# Mainboard.net
KiCad netlist of a schematic drawn in EAGLE
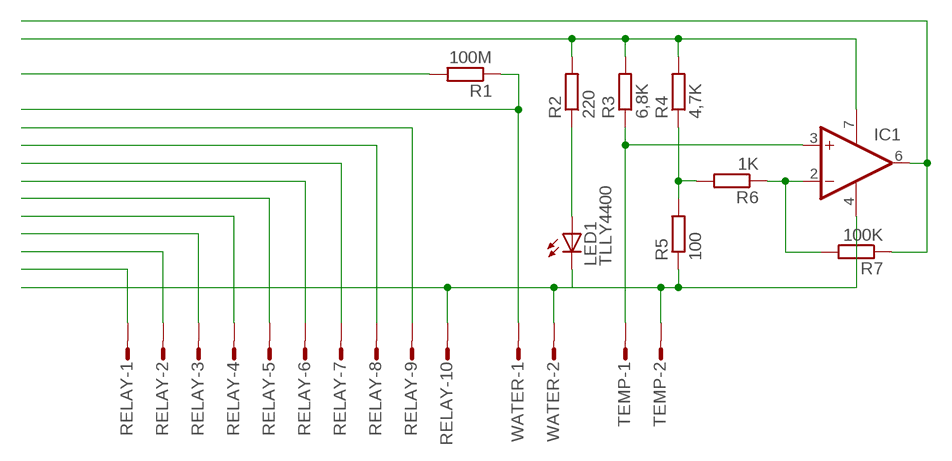
[diagram p0: schematic, sheet 1]

(export (version "E")
  (design (tool "Eeschema 10.0.6"))
  (components
    (comp (ref "IC1")
      (value "1AMP_P7+4N")
      (footprint "eagle-import:DIL08")
      (libsource (lib "eagle-import") (part "1AMP_P7+4N"))
    )
    (comp (ref "LED1")
      (value "TLLY4400")
      (footprint "eagle-import:LED3MM")
      (fields (field (name "MF") "VISHAY SEMICONDUCTOR"))
      (libsource (lib "eagle-import") (part "TLLY4400"))
    )
    (comp (ref "R1")
      (value "100M")
      (footprint "eagle-import:VMTA55")
      (libsource (lib "eagle-import") (part "R-EU_VMTA55"))
    )
    (comp (ref "R2")
      (value "220")
      (footprint "eagle-import:VMTA55")
      (libsource (lib "eagle-import") (part "R-EU_VMTA55"))
    )
    (comp (ref "R3")
      (value "6,8K")
      (footprint "eagle-import:VMTA55")
      (libsource (lib "eagle-import") (part "R-EU_VMTA55"))
    )
    (comp (ref "R4")
      (value "4,7K")
      (footprint "eagle-import:VMTA55")
      (libsource (lib "eagle-import") (part "R-EU_VMTA55"))
    )
    (comp (ref "R5")
      (value "100")
      (footprint "eagle-import:VMTA55")
      (libsource (lib "eagle-import") (part "R-EU_VMTA55"))
    )
    (comp (ref "R6")
      (value "1K")
      (footprint "eagle-import:VMTA55")
      (libsource (lib "eagle-import") (part "R-EU_VMTA55"))
    )
    (comp (ref "R7")
      (value "100K")
      (footprint "eagle-import:VMTA55")
      (libsource (lib "eagle-import") (part "R-EU_VMTA55"))
    )
    (comp (ref "RELAY")
      (value "L10P")
      (footprint "eagle-import:L10P")
      (libsource (lib "eagle-import") (part "L10P"))
    )
    (comp (ref "TEMP")
      (value "L02P")
      (footprint "eagle-import:L02P")
      (libsource (lib "eagle-import") (part "L02P"))
    )
    (comp (ref "WATER")
      (value "L02P")
      (footprint "eagle-import:L02P")
      (libsource (lib "eagle-import") (part "L02P"))
    )
  )
  (nets
    (net (code "1") (name "Net-(IC1-+IN)") (class "Default")
      (node (ref "IC1") (pin "3") (pinfunction "+IN_3") (pintype "input"))
      (node (ref "R3") (pin "1") (pinfunction "1_1") (pintype "passive"))
      (node (ref "TEMP") (pin "1") (pinfunction "S_1") (pintype "passive"))
    )
    (net (code "2") (name "Net-(IC1--IN)") (class "Default")
      (node (ref "IC1") (pin "2") (pinfunction "-IN_2") (pintype "input"))
      (node (ref "R6") (pin "1") (pinfunction "1_1") (pintype "passive"))
      (node (ref "R7") (pin "2") (pinfunction "2_2") (pintype "passive"))
    )
    (net (code "3") (name "Net-(IC1-OUT)") (class "Default")
      (node (ref "IC1") (pin "6") (pinfunction "OUT_6") (pintype "output"))
      (node (ref "R7") (pin "1") (pinfunction "1_1") (pintype "passive"))
    )
    (net (code "4") (name "Net-(IC1-V+)") (class "Default")
      (node (ref "IC1") (pin "7") (pinfunction "V+_7") (pintype "power_in"))
      (node (ref "R2") (pin "2") (pinfunction "2_2") (pintype "passive"))
      (node (ref "R3") (pin "2") (pinfunction "2_2") (pintype "passive"))
      (node (ref "R4") (pin "2") (pinfunction "2_2") (pintype "passive"))
    )
    (net (code "5") (name "Net-(IC1-V-)") (class "Default")
      (node (ref "IC1") (pin "4") (pinfunction "V-_4") (pintype "power_in"))
      (node (ref "LED1") (pin "K") (pinfunction "C_K") (pintype "passive"))
      (node (ref "R5") (pin "1") (pinfunction "1_1") (pintype "passive"))
      (node (ref "RELAY") (pin "10") (pinfunction "S_10") (pintype "passive"))
      (node (ref "TEMP") (pin "2") (pinfunction "S_2") (pintype "passive"))
      (node (ref "WATER") (pin "2") (pinfunction "S_2") (pintype "passive"))
    )
    (net (code "6") (name "Net-(LED1-PadA)") (class "Default")
      (node (ref "LED1") (pin "A") (pinfunction "A_A") (pintype "passive"))
      (node (ref "R2") (pin "1") (pinfunction "1_1") (pintype "passive"))
    )
    (net (code "7") (name "Net-(R4-Pad1)") (class "Default")
      (node (ref "R4") (pin "1") (pinfunction "1_1") (pintype "passive"))
      (node (ref "R5") (pin "2") (pinfunction "2_2") (pintype "passive"))
      (node (ref "R6") (pin "2") (pinfunction "2_2") (pintype "passive"))
    )
    (net (code "8") (name "Net-(WATERA-S)") (class "Default")
      (node (ref "R1") (pin "1") (pinfunction "1_1") (pintype "passive"))
      (node (ref "WATER") (pin "1") (pinfunction "S_1") (pintype "passive"))
    )
    (net (code "9") (name "unconnected-(R1-Pad2)") (class "Default")
      (node (ref "R1") (pin "2") (pinfunction "2_2") (pintype "passive"))
    )
    (net (code "10") (name "unconnected-(RELAYA-S-Pad1)") (class "Default")
      (node (ref "RELAY") (pin "1") (pinfunction "S_1") (pintype "passive"))
    )
    (net (code "11") (name "unconnected-(RELAYC-S-Pad2)") (class "Default")
      (node (ref "RELAY") (pin "2") (pinfunction "S_2") (pintype "passive"))
    )
    (net (code "12") (name "unconnected-(RELAYD-S-Pad3)") (class "Default")
      (node (ref "RELAY") (pin "3") (pinfunction "S_3") (pintype "passive"))
    )
    (net (code "13") (name "unconnected-(RELAYE-S-Pad4)") (class "Default")
      (node (ref "RELAY") (pin "4") (pinfunction "S_4") (pintype "passive"))
    )
    (net (code "14") (name "unconnected-(RELAYF-S-Pad5)") (class "Default")
      (node (ref "RELAY") (pin "5") (pinfunction "S_5") (pintype "passive"))
    )
    (net (code "15") (name "unconnected-(RELAYG-S-Pad6)") (class "Default")
      (node (ref "RELAY") (pin "6") (pinfunction "S_6") (pintype "passive"))
    )
    (net (code "16") (name "unconnected-(RELAYH-S-Pad7)") (class "Default")
      (node (ref "RELAY") (pin "7") (pinfunction "S_7") (pintype "passive"))
    )
    (net (code "17") (name "unconnected-(RELAYI-S-Pad8)") (class "Default")
      (node (ref "RELAY") (pin "8") (pinfunction "S_8") (pintype "passive"))
    )
    (net (code "18") (name "unconnected-(RELAYJ-S-Pad9)") (class "Default")
      (node (ref "RELAY") (pin "9") (pinfunction "S_9") (pintype "passive"))
    )
  )
)
